# 05-SERIAL_USB.net
KiCad netlist of a schematic drawn in Altium Designer
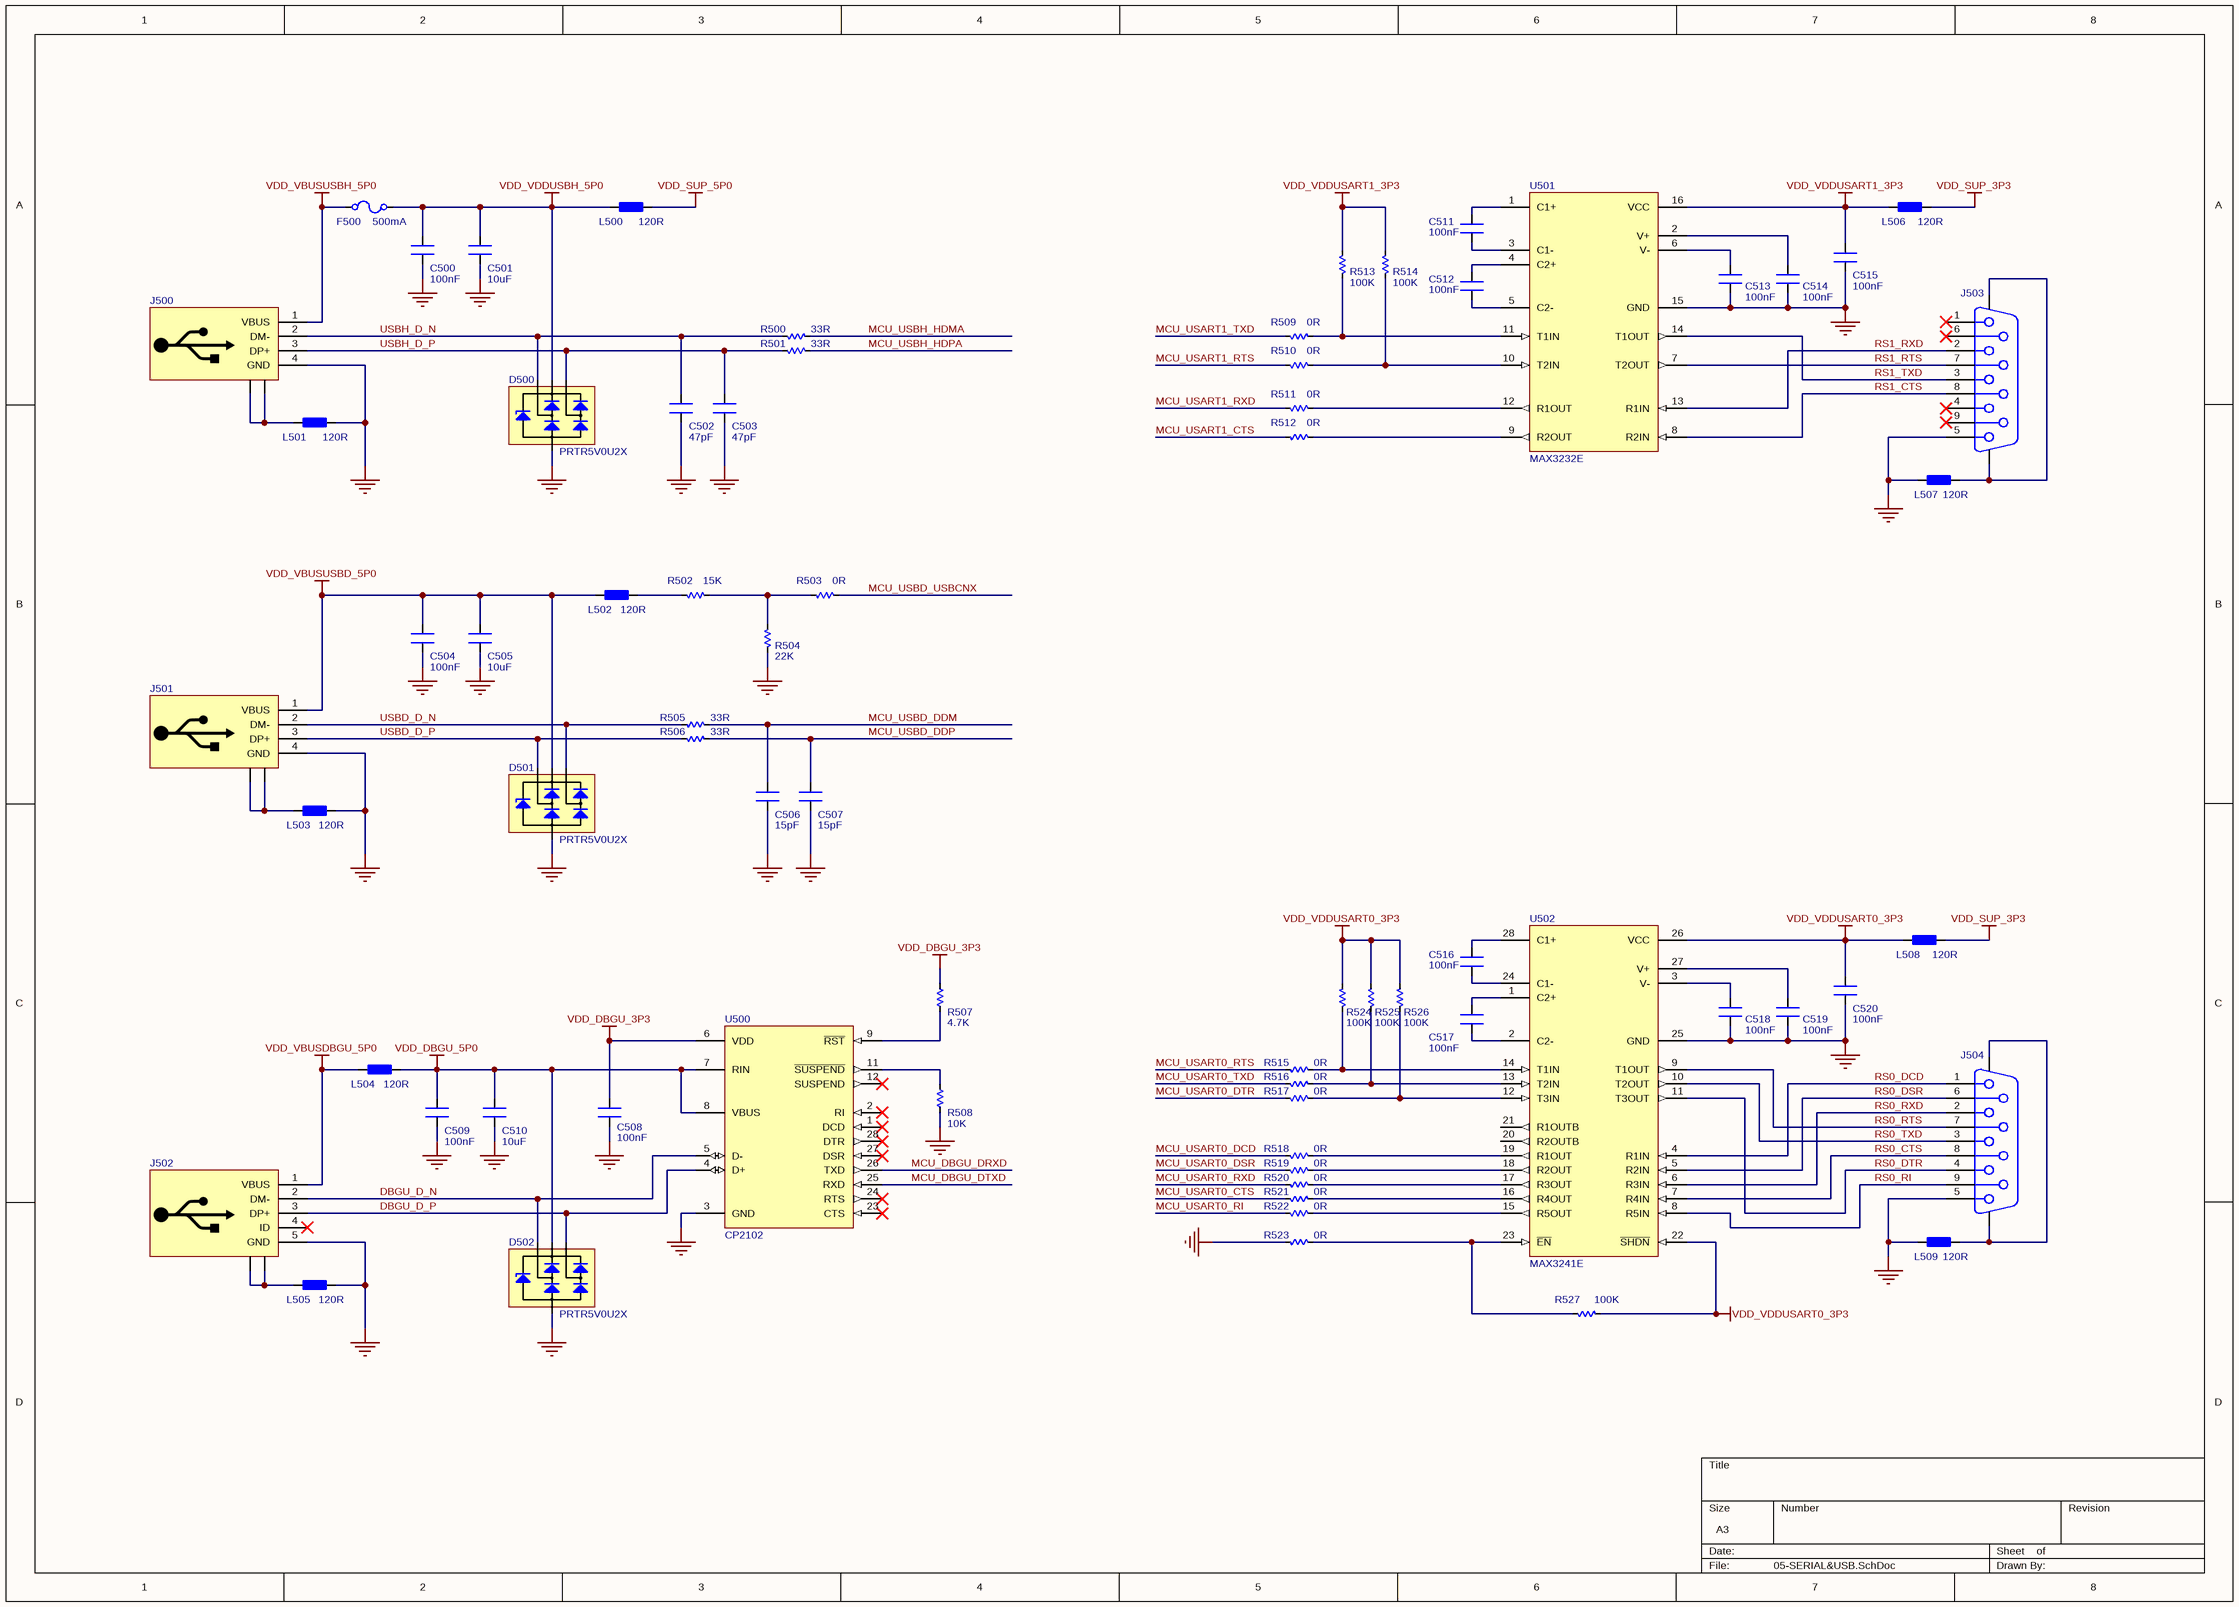
[diagram p0: 05-SERIAL&USB.SchDoc]

(export (version "E")
  (design (tool "Eeschema 10.0.6"))
  (components
    (comp (ref "C500")
      (value "100nF")
      (footprint "CN-SMD-0603")
      (description "Ceramic Capacitor SMD 0603 100nF ±20% 10V")
      (fields (field (name "Comment") "Capacitor"))
      (libsource (lib "AS50") (part "Cap"))
    )
    (comp (ref "C501")
      (value "10uF")
      (footprint "CN-SMD-0603")
      (description "Ceramic Capacitor SMD 0603 10uF ±20% 10V")
      (fields (field (name "Comment") "Capacitor"))
      (libsource (lib "AS50") (part "Cap"))
    )
    (comp (ref "C502")
      (value "47pF")
      (footprint "CN-SMD-0603")
      (description "Ceramic Capacitor SMD 0603 47pF ±20% 10V")
      (fields (field (name "Comment") "Capacitor"))
      (libsource (lib "AS50") (part "Cap"))
    )
    (comp (ref "C503")
      (value "47pF")
      (footprint "CN-SMD-0603")
      (description "Ceramic Capacitor SMD 0603 47pF ±20% 10V")
      (fields (field (name "Comment") "Capacitor"))
      (libsource (lib "AS50") (part "Cap"))
    )
    (comp (ref "C504")
      (value "100nF")
      (footprint "CN-SMD-0603")
      (description "Ceramic Capacitor SMD 0603 100nF ±20% 10V")
      (fields (field (name "Comment") "Capacitor"))
      (libsource (lib "AS50") (part "Cap"))
    )
    (comp (ref "C505")
      (value "10uF")
      (footprint "CN-SMD-0603")
      (description "Ceramic Capacitor SMD 0603 10uF ±20% 10V")
      (fields (field (name "Comment") "Capacitor"))
      (libsource (lib "AS50") (part "Cap"))
    )
    (comp (ref "C506")
      (value "15pF")
      (footprint "CN-SMD-0603")
      (description "Ceramic Capacitor SMD 0603 15pF ±20% 10V")
      (fields (field (name "Comment") "Capacitor"))
      (libsource (lib "AS50") (part "Cap"))
    )
    (comp (ref "C507")
      (value "15pF")
      (footprint "CN-SMD-0603")
      (description "Ceramic Capacitor SMD 0603 15pF ±20% 10V")
      (fields (field (name "Comment") "Capacitor"))
      (libsource (lib "AS50") (part "Cap"))
    )
    (comp (ref "C508")
      (value "100nF")
      (footprint "CN-SMD-0603")
      (description "Ceramic Capacitor SMD 0603 100nF ±20% 10V")
      (fields (field (name "Comment") "Capacitor"))
      (libsource (lib "AS50") (part "Cap"))
    )
    (comp (ref "C509")
      (value "100nF")
      (footprint "CN-SMD-0603")
      (description "Ceramic Capacitor SMD 0603 100nF ±20% 10V")
      (fields (field (name "Comment") "Capacitor"))
      (libsource (lib "AS50") (part "Cap"))
    )
    (comp (ref "C510")
      (value "10uF")
      (footprint "CN-SMD-0603")
      (description "Ceramic Capacitor SMD 0603 10uF ±20% 10V")
      (fields (field (name "Comment") "Capacitor"))
      (libsource (lib "AS50") (part "Cap"))
    )
    (comp (ref "C511")
      (value "100nF")
      (footprint "CN-SMD-0603")
      (description "Ceramic Capacitor SMD 0603 100nF ±20% 10V")
      (fields (field (name "Comment") "Capacitor"))
      (libsource (lib "AS50") (part "Cap"))
    )
    (comp (ref "C512")
      (value "100nF")
      (footprint "CN-SMD-0603")
      (description "Ceramic Capacitor SMD 0603 100nF ±20% 10V")
      (fields (field (name "Comment") "Capacitor"))
      (libsource (lib "AS50") (part "Cap"))
    )
    (comp (ref "C513")
      (value "100nF")
      (footprint "CN-SMD-0603")
      (description "Ceramic Capacitor SMD 0603 100nF ±20% 10V")
      (fields (field (name "Comment") "Capacitor"))
      (libsource (lib "AS50") (part "Cap"))
    )
    (comp (ref "C514")
      (value "100nF")
      (footprint "CN-SMD-0603")
      (description "Ceramic Capacitor SMD 0603 100nF ±20% 10V")
      (fields (field (name "Comment") "Capacitor"))
      (libsource (lib "AS50") (part "Cap"))
    )
    (comp (ref "C515")
      (value "100nF")
      (footprint "CN-SMD-0603")
      (description "Ceramic Capacitor SMD 0603 100nF ±20% 10V")
      (fields (field (name "Comment") "Capacitor"))
      (libsource (lib "AS50") (part "Cap"))
    )
    (comp (ref "C516")
      (value "100nF")
      (footprint "CN-SMD-0603")
      (description "Ceramic Capacitor SMD 0603 100nF ±20% 10V")
      (fields (field (name "Comment") "Capacitor"))
      (libsource (lib "AS50") (part "Cap"))
    )
    (comp (ref "C517")
      (value "100nF")
      (footprint "CN-SMD-0603")
      (description "Ceramic Capacitor SMD 0603 100nF ±20% 10V")
      (fields (field (name "Comment") "Capacitor"))
      (libsource (lib "AS50") (part "Cap"))
    )
    (comp (ref "C518")
      (value "100nF")
      (footprint "CN-SMD-0603")
      (description "Ceramic Capacitor SMD 0603 100nF ±20% 10V")
      (fields (field (name "Comment") "Capacitor"))
      (libsource (lib "AS50") (part "Cap"))
    )
    (comp (ref "C519")
      (value "100nF")
      (footprint "CN-SMD-0603")
      (description "Ceramic Capacitor SMD 0603 100nF ±20% 10V")
      (fields (field (name "Comment") "Capacitor"))
      (libsource (lib "AS50") (part "Cap"))
    )
    (comp (ref "C520")
      (value "100nF")
      (footprint "CN-SMD-0603")
      (description "Ceramic Capacitor SMD 0603 100nF ±20% 10V")
      (fields (field (name "Comment") "Capacitor"))
      (libsource (lib "AS50") (part "Cap"))
    )
    (comp (ref "D500")
      (value "PRTR5V0U2X")
      (footprint "SOT190P237X120-4N")
      (description "Ultra low capacitance double rail-to-rail ESD protection diode")
      (libsource (lib "AS50") (part "PRTR5V0U2X"))
    )
    (comp (ref "D501")
      (value "PRTR5V0U2X")
      (footprint "SOT190P237X120-4N")
      (description "Ultra low capacitance double rail-to-rail ESD protection diode")
      (libsource (lib "AS50") (part "PRTR5V0U2X"))
    )
    (comp (ref "D502")
      (value "PRTR5V0U2X")
      (footprint "SOT190P237X120-4N")
      (description "Ultra low capacitance double rail-to-rail ESD protection diode")
      (libsource (lib "AS50") (part "PRTR5V0U2X"))
    )
    (comp (ref "F500")
      (value "500mA")
      (footprint "FUSE-SMD-1812")
      (description "Fuse SMD1812 500mA")
      (libsource (lib "AS50") (part "FUSE"))
    )
    (comp (ref "J500")
      (value "USB-4")
      (footprint "USB_A_F_DIP_RA")
      (description "USB Male/Female type A")
      (libsource (lib "AS50") (part "USB-4"))
    )
    (comp (ref "J501")
      (value "USB-4")
      (footprint "USB_B_F_DIP")
      (description "USB Male/Female type B")
      (libsource (lib "AS50") (part "USB-4"))
    )
    (comp (ref "J502")
      (value "USB-5")
      (footprint "USB_micro-B_F_SMD-2")
      (description "USB Female type B")
      (libsource (lib "AS50") (part "USB-5"))
    )
    (comp (ref "J503")
      (value "DB9")
      (footprint "DB9_DIP_M")
      (description "DB-9 Female port")
      (libsource (lib "AS50") (part "DB9"))
    )
    (comp (ref "J504")
      (value "DB9")
      (footprint "DB9_DIP_M")
      (description "DB-9 Female port")
      (libsource (lib "AS50") (part "DB9"))
    )
    (comp (ref "L500")
      (value "120R")
      (footprint "L-SMD-0603")
      (description "Ferrite bead SMD 0603 120 Ohm @100MHz")
      (fields (field (name "Comment") "Ferrite bead"))
      (libsource (lib "AS50") (part "Ferrite bead"))
    )
    (comp (ref "L501")
      (value "120R")
      (footprint "L-SMD-0603")
      (description "Ferrite bead SMD 0603 120 Ohm @100MHz")
      (fields (field (name "Comment") "Ferrite bead"))
      (libsource (lib "AS50") (part "Ferrite bead"))
    )
    (comp (ref "L502")
      (value "120R")
      (footprint "L-SMD-0603")
      (description "Ferrite bead SMD 0603 120 Ohm @100MHz")
      (fields (field (name "Comment") "Ferrite bead"))
      (libsource (lib "AS50") (part "Ferrite bead"))
    )
    (comp (ref "L503")
      (value "120R")
      (footprint "L-SMD-0603")
      (description "Ferrite bead SMD 0603 120 Ohm @100MHz")
      (fields (field (name "Comment") "Ferrite bead"))
      (libsource (lib "AS50") (part "Ferrite bead"))
    )
    (comp (ref "L504")
      (value "120R")
      (footprint "L-SMD-0603")
      (description "Ferrite bead SMD 0603 120 Ohm @100MHz")
      (fields (field (name "Comment") "Ferrite bead"))
      (libsource (lib "AS50") (part "Ferrite bead"))
    )
    (comp (ref "L505")
      (value "120R")
      (footprint "L-SMD-0603")
      (description "Ferrite bead SMD 0603 120 Ohm @100MHz")
      (fields (field (name "Comment") "Ferrite bead"))
      (libsource (lib "AS50") (part "Ferrite bead"))
    )
    (comp (ref "L506")
      (value "120R")
      (footprint "L-SMD-0603")
      (description "Ferrite bead SMD 0603 120 Ohm @100MHz")
      (fields (field (name "Comment") "Ferrite bead"))
      (libsource (lib "AS50") (part "Ferrite bead"))
    )
    (comp (ref "L507")
      (value "120R")
      (footprint "L-SMD-0603")
      (description "Ferrite bead SMD 0603 120 Ohm @100MHz")
      (fields (field (name "Comment") "Ferrite bead"))
      (libsource (lib "AS50") (part "Ferrite bead"))
    )
    (comp (ref "L508")
      (value "120R")
      (footprint "L-SMD-0603")
      (description "Ferrite bead SMD 0603 120 Ohm @100MHz")
      (fields (field (name "Comment") "Ferrite bead"))
      (libsource (lib "AS50") (part "Ferrite bead"))
    )
    (comp (ref "L509")
      (value "120R")
      (footprint "L-SMD-0603")
      (description "Ferrite bead SMD 0603 120 Ohm @100MHz")
      (fields (field (name "Comment") "Ferrite bead"))
      (libsource (lib "AS50") (part "Ferrite bead"))
    )
    (comp (ref "R500")
      (value "33R")
      (footprint "RES-SMD-0603")
      (description "Resistor SMD 0603 33R 1% 0.1W")
      (fields (field (name "Comment") "Resistor"))
      (libsource (lib "AS50") (part "Res"))
    )
    (comp (ref "R501")
      (value "33R")
      (footprint "RES-SMD-0603")
      (description "Resistor SMD 0603 33R 1% 0.1W")
      (fields (field (name "Comment") "Resistor"))
      (libsource (lib "AS50") (part "Res"))
    )
    (comp (ref "R502")
      (value "15K")
      (footprint "RES-SMD-0603")
      (description "Resistor SMD 0603 15K 1% 0.1W")
      (fields (field (name "Comment") "Resistor"))
      (libsource (lib "AS50") (part "Res"))
    )
    (comp (ref "R503")
      (value "0R")
      (footprint "RES-SMD-0603")
      (description "Resistor SMD 0603 0R 1% 0.1W")
      (fields (field (name "Comment") "Resistor"))
      (libsource (lib "AS50") (part "Res"))
    )
    (comp (ref "R504")
      (value "22K")
      (footprint "RES-SMD-0603")
      (description "Resistor SMD 0603 22K 1% 0.1W")
      (fields (field (name "Comment") "Resistor"))
      (libsource (lib "AS50") (part "Res"))
    )
    (comp (ref "R505")
      (value "33R")
      (footprint "RES-SMD-0603")
      (description "Resistor SMD 0603 33R 1% 0.1W")
      (fields (field (name "Comment") "Resistor"))
      (libsource (lib "AS50") (part "Res"))
    )
    (comp (ref "R506")
      (value "33R")
      (footprint "RES-SMD-0603")
      (description "Resistor SMD 0603 33R 1% 0.1W")
      (fields (field (name "Comment") "Resistor"))
      (libsource (lib "AS50") (part "Res"))
    )
    (comp (ref "R507")
      (value "4.7K")
      (footprint "RES-SMD-0603")
      (description "Resistor SMD 0603 4.7K 1% 0.1W")
      (fields (field (name "Comment") "R"))
      (libsource (lib "AS50") (part "Res"))
    )
    (comp (ref "R508")
      (value "10K")
      (footprint "RES-SMD-0603")
      (description "Resistor SMD 0603 10K 1% 0.1W")
      (fields (field (name "Comment") "R"))
      (libsource (lib "AS50") (part "Res"))
    )
    (comp (ref "R509")
      (value "0R")
      (footprint "RES-SMD-0603")
      (description "Resistor SMD 0603 0R 1% 0.1W")
      (fields (field (name "Comment") "Resistor"))
      (libsource (lib "AS50") (part "Res"))
    )
    (comp (ref "R510")
      (value "0R")
      (footprint "RES-SMD-0603")
      (description "Resistor SMD 0603 0R 1% 0.1W")
      (fields (field (name "Comment") "Resistor"))
      (libsource (lib "AS50") (part "Res"))
    )
    (comp (ref "R511")
      (value "0R")
      (footprint "RES-SMD-0603")
      (description "Resistor SMD 0603 0R 1% 0.1W")
      (fields (field (name "Comment") "Resistor"))
      (libsource (lib "AS50") (part "Res"))
    )
    (comp (ref "R512")
      (value "0R")
      (footprint "RES-SMD-0603")
      (description "Resistor SMD 0603 0R 1% 0.1W")
      (fields (field (name "Comment") "Resistor"))
      (libsource (lib "AS50") (part "Res"))
    )
    (comp (ref "R513")
      (value "100K")
      (footprint "RES-SMD-0603")
      (description "Resistor SMD 0603 100K 1% 0.1W")
      (fields (field (name "Comment") "Resistor"))
      (libsource (lib "AS50") (part "Res"))
    )
    (comp (ref "R514")
      (value "100K")
      (footprint "RES-SMD-0603")
      (description "Resistor SMD 0603 100K 1% 0.1W")
      (fields (field (name "Comment") "Resistor"))
      (libsource (lib "AS50") (part "Res"))
    )
    (comp (ref "R515")
      (value "0R")
      (footprint "RES-SMD-0603")
      (description "Resistor SMD 0603 0R 1% 0.1W")
      (fields (field (name "Comment") "Resistor"))
      (libsource (lib "AS50") (part "Res"))
    )
    (comp (ref "R516")
      (value "0R")
      (footprint "RES-SMD-0603")
      (description "Resistor SMD 0603 0R 1% 0.1W")
      (fields (field (name "Comment") "Resistor"))
      (libsource (lib "AS50") (part "Res"))
    )
    (comp (ref "R517")
      (value "0R")
      (footprint "RES-SMD-0603")
      (description "Resistor SMD 0603 0R 1% 0.1W")
      (fields (field (name "Comment") "Resistor"))
      (libsource (lib "AS50") (part "Res"))
    )
    (comp (ref "R518")
      (value "0R")
      (footprint "RES-SMD-0603")
      (description "Resistor SMD 0603 0R 1% 0.1W")
      (fields (field (name "Comment") "Resistor"))
      (libsource (lib "AS50") (part "Res"))
    )
    (comp (ref "R519")
      (value "0R")
      (footprint "RES-SMD-0603")
      (description "Resistor SMD 0603 0R 1% 0.1W")
      (fields (field (name "Comment") "Resistor"))
      (libsource (lib "AS50") (part "Res"))
    )
    (comp (ref "R520")
      (value "0R")
      (footprint "RES-SMD-0603")
      (description "Resistor SMD 0603 0R 1% 0.1W")
      (fields (field (name "Comment") "Resistor"))
      (libsource (lib "AS50") (part "Res"))
    )
    (comp (ref "R521")
      (value "0R")
      (footprint "RES-SMD-0603")
      (description "Resistor SMD 0603 0R 1% 0.1W")
      (fields (field (name "Comment") "Resistor"))
      (libsource (lib "AS50") (part "Res"))
    )
    (comp (ref "R522")
      (value "0R")
      (footprint "RES-SMD-0603")
      (description "Resistor SMD 0603 0R 1% 0.1W")
      (fields (field (name "Comment") "Resistor"))
      (libsource (lib "AS50") (part "Res"))
    )
    (comp (ref "R523")
      (value "0R")
      (footprint "RES-SMD-0603")
      (description "Resistor SMD 0603 0R 1% 0.1W")
      (fields (field (name "Comment") "Resistor"))
      (libsource (lib "AS50") (part "Res"))
    )
    (comp (ref "R524")
      (value "100K")
      (footprint "RES-SMD-0603")
      (description "Resistor SMD 0603 100K 1% 0.1W")
      (fields (field (name "Comment") "Resistor"))
      (libsource (lib "AS50") (part "Res"))
    )
    (comp (ref "R525")
      (value "100K")
      (footprint "RES-SMD-0603")
      (description "Resistor SMD 0603 100K 1% 0.1W")
      (fields (field (name "Comment") "Resistor"))
      (libsource (lib "AS50") (part "Res"))
    )
    (comp (ref "R526")
      (value "100K")
      (footprint "RES-SMD-0603")
      (description "Resistor SMD 0603 100K 1% 0.1W")
      (fields (field (name "Comment") "Resistor"))
      (libsource (lib "AS50") (part "Res"))
    )
    (comp (ref "R527")
      (value "100K")
      (footprint "RES-SMD-0603")
      (description "Resistor SMD 0603 100K 1% 0.1W")
      (fields (field (name "Comment") "Resistor"))
      (libsource (lib "AS50") (part "Res"))
    )
    (comp (ref "U500")
      (value "CP2102")
      (footprint "QFN50P500X500X100_HS-29N")
      (description "Single chip USB-to-UART Bridge")
      (libsource (lib "AS50") (part "CP2102"))
    )
    (comp (ref "U501")
      (value "MAX3232E")
      (footprint "TSSOP65P640X120-16N")
      (libsource (lib "AS50") (part "MAX3232E"))
    )
    (comp (ref "U502")
      (value "MAX3241E")
      (footprint "SSOP65P780X200-28N")
      (libsource (lib "AS50") (part "MAX3241E"))
    )
  )
  (nets
    (net (code "1") (name "/DBGU_D_N") (class "Default")
      (node (ref "D502") (pin "2") (pintype "passive"))
      (node (ref "J502") (pin "2") (pinfunction "DM-_2") (pintype "passive"))
      (node (ref "U500") (pin "5") (pinfunction "D-_5") (pintype "bidirectional"))
    )
    (net (code "2") (name "/DBGU_D_P") (class "Default")
      (node (ref "D502") (pin "3") (pintype "passive"))
      (node (ref "J502") (pin "3") (pinfunction "DP+_3") (pintype "passive"))
      (node (ref "U500") (pin "4") (pinfunction "D+_4") (pintype "bidirectional"))
    )
    (net (code "3") (name "/MCU_DBGU_DRXD") (class "Default")
      (node (ref "U500") (pin "26") (pinfunction "TXD_26") (pintype "output"))
    )
    (net (code "4") (name "/MCU_DBGU_DTXD") (class "Default")
      (node (ref "U500") (pin "25") (pinfunction "RXD_25") (pintype "input"))
    )
    (net (code "5") (name "/MCU_USART0_CTS") (class "Default")
      (node (ref "R521") (pin "2") (pinfunction "2_2") (pintype "passive"))
    )
    (net (code "6") (name "/MCU_USART0_DCD") (class "Default")
      (node (ref "R518") (pin "2") (pinfunction "2_2") (pintype "passive"))
    )
    (net (code "7") (name "/MCU_USART0_DSR") (class "Default")
      (node (ref "R519") (pin "2") (pinfunction "2_2") (pintype "passive"))
    )
    (net (code "8") (name "/MCU_USART0_DTR") (class "Default")
      (node (ref "R517") (pin "2") (pinfunction "2_2") (pintype "passive"))
    )
    (net (code "9") (name "/MCU_USART0_RI") (class "Default")
      (node (ref "R522") (pin "2") (pinfunction "2_2") (pintype "passive"))
    )
    (net (code "10") (name "/MCU_USART0_RTS") (class "Default")
      (node (ref "R515") (pin "2") (pinfunction "2_2") (pintype "passive"))
    )
    (net (code "11") (name "/MCU_USART0_RXD") (class "Default")
      (node (ref "R520") (pin "2") (pinfunction "2_2") (pintype "passive"))
    )
    (net (code "12") (name "/MCU_USART0_TXD") (class "Default")
      (node (ref "R516") (pin "2") (pinfunction "2_2") (pintype "passive"))
    )
    (net (code "13") (name "/MCU_USART1_CTS") (class "Default")
      (node (ref "R512") (pin "2") (pinfunction "2_2") (pintype "passive"))
    )
    (net (code "14") (name "/MCU_USART1_RTS") (class "Default")
      (node (ref "R510") (pin "2") (pinfunction "2_2") (pintype "passive"))
    )
    (net (code "15") (name "/MCU_USART1_RXD") (class "Default")
      (node (ref "R511") (pin "2") (pinfunction "2_2") (pintype "passive"))
    )
    (net (code "16") (name "/MCU_USART1_TXD") (class "Default")
      (node (ref "R509") (pin "2") (pinfunction "2_2") (pintype "passive"))
    )
    (net (code "17") (name "/MCU_USBD_DDM") (class "Default")
      (node (ref "C506") (pin "2") (pinfunction "2_2") (pintype "passive"))
      (node (ref "R505") (pin "1") (pinfunction "1_1") (pintype "passive"))
    )
    (net (code "18") (name "/MCU_USBD_DDP") (class "Default")
      (node (ref "C507") (pin "2") (pinfunction "2_2") (pintype "passive"))
      (node (ref "R506") (pin "1") (pinfunction "1_1") (pintype "passive"))
    )
    (net (code "19") (name "/MCU_USBD_USBCNX") (class "Default")
      (node (ref "R503") (pin "1") (pinfunction "1_1") (pintype "passive"))
    )
    (net (code "20") (name "/MCU_USBH_HDMA") (class "Default")
      (node (ref "R500") (pin "1") (pinfunction "1_1") (pintype "passive"))
    )
    (net (code "21") (name "/MCU_USBH_HDPA") (class "Default")
      (node (ref "R501") (pin "1") (pinfunction "1_1") (pintype "passive"))
    )
    (net (code "22") (name "/RS0_CTS") (class "Default")
      (node (ref "J504") (pin "8") (pinfunction "CTS_8") (pintype "passive"))
      (node (ref "U502") (pin "7") (pinfunction "R4IN_7") (pintype "input"))
    )
    (net (code "23") (name "/RS0_DCD") (class "Default")
      (node (ref "J504") (pin "1") (pinfunction "DCD_1") (pintype "passive"))
      (node (ref "U502") (pin "4") (pinfunction "R1IN_4") (pintype "input"))
    )
    (net (code "24") (name "/RS0_DSR") (class "Default")
      (node (ref "J504") (pin "6") (pinfunction "DSR_6") (pintype "passive"))
      (node (ref "U502") (pin "5") (pinfunction "R2IN_5") (pintype "input"))
    )
    (net (code "25") (name "/RS0_DTR") (class "Default")
      (node (ref "J504") (pin "4") (pinfunction "DTR_4") (pintype "passive"))
      (node (ref "U502") (pin "11") (pinfunction "T3OUT_11") (pintype "output"))
    )
    (net (code "26") (name "/RS0_RI") (class "Default")
      (node (ref "J504") (pin "9") (pinfunction "RI_9") (pintype "passive"))
      (node (ref "U502") (pin "8") (pinfunction "R5IN_8") (pintype "input"))
    )
    (net (code "27") (name "/RS0_RTS") (class "Default")
      (node (ref "J504") (pin "7") (pinfunction "RTS_7") (pintype "passive"))
      (node (ref "U502") (pin "9") (pinfunction "T1OUT_9") (pintype "output"))
    )
    (net (code "28") (name "/RS0_RXD") (class "Default")
      (node (ref "J504") (pin "2") (pinfunction "RXD_2") (pintype "passive"))
      (node (ref "U502") (pin "6") (pinfunction "R3IN_6") (pintype "input"))
    )
    (net (code "29") (name "/RS0_TXD") (class "Default")
      (node (ref "J504") (pin "3") (pinfunction "TXD_3") (pintype "passive"))
      (node (ref "U502") (pin "10") (pinfunction "T2OUT_10") (pintype "output"))
    )
    (net (code "30") (name "/RS1_CTS") (class "Default")
      (node (ref "J503") (pin "8") (pinfunction "CTS_8") (pintype "passive"))
      (node (ref "U501") (pin "8") (pinfunction "R2IN_8") (pintype "input"))
    )
    (net (code "31") (name "/RS1_RTS") (class "Default")
      (node (ref "J503") (pin "7") (pinfunction "RTS_7") (pintype "passive"))
      (node (ref "U501") (pin "7") (pinfunction "T2OUT_7") (pintype "output"))
    )
    (net (code "32") (name "/RS1_RXD") (class "Default")
      (node (ref "J503") (pin "2") (pinfunction "RXD_2") (pintype "passive"))
      (node (ref "U501") (pin "13") (pinfunction "R1IN_13") (pintype "input"))
    )
    (net (code "33") (name "/RS1_TXD") (class "Default")
      (node (ref "J503") (pin "3") (pinfunction "TXD_3") (pintype "passive"))
      (node (ref "U501") (pin "14") (pinfunction "T1OUT_14") (pintype "output"))
    )
    (net (code "34") (name "/USBD_D_N") (class "Default")
      (node (ref "D501") (pin "3") (pintype "passive"))
      (node (ref "J501") (pin "2") (pinfunction "DM-_2") (pintype "passive"))
      (node (ref "R505") (pin "2") (pinfunction "2_2") (pintype "passive"))
    )
    (net (code "35") (name "/USBD_D_P") (class "Default")
      (node (ref "D501") (pin "2") (pintype "passive"))
      (node (ref "J501") (pin "3") (pinfunction "DP+_3") (pintype "passive"))
      (node (ref "R506") (pin "2") (pinfunction "2_2") (pintype "passive"))
    )
    (net (code "36") (name "/USBH_D_N") (class "Default")
      (node (ref "C502") (pin "2") (pinfunction "2_2") (pintype "passive"))
      (node (ref "D500") (pin "2") (pintype "passive"))
      (node (ref "J500") (pin "2") (pinfunction "DM-_2") (pintype "passive"))
      (node (ref "R500") (pin "2") (pinfunction "2_2") (pintype "passive"))
    )
    (net (code "37") (name "/USBH_D_P") (class "Default")
      (node (ref "C503") (pin "2") (pinfunction "2_2") (pintype "passive"))
      (node (ref "D500") (pin "3") (pintype "passive"))
      (node (ref "J500") (pin "3") (pinfunction "DP+_3") (pintype "passive"))
      (node (ref "R501") (pin "2") (pinfunction "2_2") (pintype "passive"))
    )
    (net (code "38") (name "GND") (class "Default")
      (node (ref "C500") (pin "1") (pinfunction "1_1") (pintype "passive"))
      (node (ref "C501") (pin "1") (pinfunction "1_1") (pintype "passive"))
      (node (ref "C502") (pin "1") (pinfunction "1_1") (pintype "passive"))
      (node (ref "C503") (pin "1") (pinfunction "1_1") (pintype "passive"))
      (node (ref "C504") (pin "1") (pinfunction "1_1") (pintype "passive"))
      (node (ref "C505") (pin "1") (pinfunction "1_1") (pintype "passive"))
      (node (ref "C506") (pin "1") (pinfunction "1_1") (pintype "passive"))
      (node (ref "C507") (pin "1") (pinfunction "1_1") (pintype "passive"))
      (node (ref "C508") (pin "1") (pinfunction "1_1") (pintype "passive"))
      (node (ref "C509") (pin "1") (pinfunction "1_1") (pintype "passive"))
      (node (ref "C510") (pin "1") (pinfunction "1_1") (pintype "passive"))
      (node (ref "C513") (pin "1") (pinfunction "1_1") (pintype "passive"))
      (node (ref "C514") (pin "1") (pinfunction "1_1") (pintype "passive"))
      (node (ref "C515") (pin "1") (pinfunction "1_1") (pintype "passive"))
      (node (ref "C518") (pin "1") (pinfunction "1_1") (pintype "passive"))
      (node (ref "C519") (pin "1") (pinfunction "1_1") (pintype "passive"))
      (node (ref "C520") (pin "1") (pinfunction "1_1") (pintype "passive"))
      (node (ref "D500") (pin "1") (pinfunction "GND_1") (pintype "passive"))
      (node (ref "D501") (pin "1") (pinfunction "GND_1") (pintype "passive"))
      (node (ref "D502") (pin "1") (pinfunction "GND_1") (pintype "passive"))
      (node (ref "J500") (pin "4") (pinfunction "GND_4") (pintype "passive"))
      (node (ref "J501") (pin "4") (pinfunction "GND_4") (pintype "passive"))
      (node (ref "J502") (pin "5") (pinfunction "GND_5") (pintype "passive"))
      (node (ref "J503") (pin "5") (pinfunction "GND_5") (pintype "passive"))
      (node (ref "J504") (pin "5") (pinfunction "GND_5") (pintype "passive"))
      (node (ref "L501") (pin "1") (pinfunction "1_1") (pintype "passive"))
      (node (ref "L503") (pin "2") (pinfunction "2_2") (pintype "passive"))
      (node (ref "L505") (pin "2") (pinfunction "2_2") (pintype "passive"))
      (node (ref "L507") (pin "1") (pinfunction "1_1") (pintype "passive"))
      (node (ref "L509") (pin "1") (pinfunction "1_1") (pintype "passive"))
      (node (ref "R504") (pin "2") (pinfunction "2_2") (pintype "passive"))
      (node (ref "R508") (pin "1") (pinfunction "1_1") (pintype "passive"))
      (node (ref "R523") (pin "2") (pinfunction "2_2") (pintype "passive"))
      (node (ref "U500") (pin "3") (pinfunction "GND_3") (pintype "power_in"))
      (node (ref "U501") (pin "15") (pinfunction "GND_15") (pintype "power_in"))
      (node (ref "U502") (pin "25") (pinfunction "GND_25") (pintype "power_in"))
    )
    (net (code "39") (name "Net-(J500-Pad0)") (class "Default")
      (node (ref "J500") (pin "0") (pintype "power_in"))
      (node (ref "L501") (pin "2") (pinfunction "2_2") (pintype "passive"))
    )
    (net (code "40") (name "Net-(J501-Pad0)") (class "Default")
      (node (ref "J501") (pin "0") (pintype "power_in"))
      (node (ref "L503") (pin "1") (pinfunction "1_1") (pintype "passive"))
    )
    (net (code "41") (name "Net-(J502-Pad0)") (class "Default")
      (node (ref "J502") (pin "0") (pintype "power_in"))
      (node (ref "L505") (pin "1") (pinfunction "1_1") (pintype "passive"))
    )
    (net (code "42") (name "Net-(J503-Pad10)") (class "Default")
      (node (ref "J503") (pin "10") (pintype "passive"))
      (node (ref "J503") (pin "11") (pintype "passive"))
      (node (ref "L507") (pin "2") (pinfunction "2_2") (pintype "passive"))
    )
    (net (code "43") (name "Net-(J504-Pad10)") (class "Default")
      (node (ref "J504") (pin "10") (pintype "passive"))
      (node (ref "J504") (pin "11") (pintype "passive"))
      (node (ref "L509") (pin "2") (pinfunction "2_2") (pintype "passive"))
    )
    (net (code "44") (name "Net-(L502-Pad2)") (class "Default")
      (node (ref "L502") (pin "2") (pinfunction "2_2") (pintype "passive"))
      (node (ref "R502") (pin "2") (pinfunction "2_2") (pintype "passive"))
    )
    (net (code "45") (name "Net-(R502-Pad1)") (class "Default")
      (node (ref "R502") (pin "1") (pinfunction "1_1") (pintype "passive"))
      (node (ref "R503") (pin "2") (pinfunction "2_2") (pintype "passive"))
      (node (ref "R504") (pin "1") (pinfunction "1_1") (pintype "passive"))
    )
    (net (code "46") (name "Net-(U500-~{RST})") (class "Default")
      (node (ref "R507") (pin "1") (pinfunction "1_1") (pintype "passive"))
      (node (ref "U500") (pin "9") (pinfunction "~{RST}_9") (pintype "input"))
    )
    (net (code "47") (name "Net-(U500-~{SUSPEND})") (class "Default")
      (node (ref "R508") (pin "2") (pinfunction "2_2") (pintype "passive"))
      (node (ref "U500") (pin "11") (pinfunction "~{SUSPEND}_11") (pintype "output"))
    )
    (net (code "48") (name "Net-(U501-C1+)") (class "Default")
      (node (ref "C511") (pin "2") (pinfunction "2_2") (pintype "passive"))
      (node (ref "U501") (pin "1") (pinfunction "C1+_1") (pintype "passive"))
    )
    (net (code "49") (name "Net-(U501-C1-)") (class "Default")
      (node (ref "C511") (pin "1") (pinfunction "1_1") (pintype "passive"))
      (node (ref "U501") (pin "3") (pinfunction "C1-_3") (pintype "passive"))
    )
    (net (code "50") (name "Net-(U501-C2+)") (class "Default")
      (node (ref "C512") (pin "2") (pinfunction "2_2") (pintype "passive"))
      (node (ref "U501") (pin "4") (pinfunction "C2+_4") (pintype "passive"))
    )
    (net (code "51") (name "Net-(U501-C2-)") (class "Default")
      (node (ref "C512") (pin "1") (pinfunction "1_1") (pintype "passive"))
      (node (ref "U501") (pin "5") (pinfunction "C2-_5") (pintype "passive"))
    )
    (net (code "52") (name "Net-(U501-R1OUT)") (class "Default")
      (node (ref "R511") (pin "1") (pinfunction "1_1") (pintype "passive"))
      (node (ref "U501") (pin "12") (pinfunction "R1OUT_12") (pintype "output"))
    )
    (net (code "53") (name "Net-(U501-R2OUT)") (class "Default")
      (node (ref "R512") (pin "1") (pinfunction "1_1") (pintype "passive"))
      (node (ref "U501") (pin "9") (pinfunction "R2OUT_9") (pintype "output"))
    )
    (net (code "54") (name "Net-(U501-T1IN)") (class "Default")
      (node (ref "R509") (pin "1") (pinfunction "1_1") (pintype "passive"))
      (node (ref "R513") (pin "2") (pinfunction "2_2") (pintype "passive"))
      (node (ref "U501") (pin "11") (pinfunction "T1IN_11") (pintype "input"))
    )
    (net (code "55") (name "Net-(U501-T2IN)") (class "Default")
      (node (ref "R510") (pin "1") (pinfunction "1_1") (pintype "passive"))
      (node (ref "R514") (pin "2") (pinfunction "2_2") (pintype "passive"))
      (node (ref "U501") (pin "10") (pinfunction "T2IN_10") (pintype "input"))
    )
    (net (code "56") (name "Net-(U501-V+)") (class "Default")
      (node (ref "C514") (pin "2") (pinfunction "2_2") (pintype "passive"))
      (node (ref "U501") (pin "2") (pinfunction "V+_2") (pintype "power_in"))
    )
    (net (code "57") (name "Net-(U501-V-)") (class "Default")
      (node (ref "C513") (pin "2") (pinfunction "2_2") (pintype "passive"))
      (node (ref "U501") (pin "6") (pinfunction "V-_6") (pintype "power_in"))
    )
    (net (code "58") (name "Net-(U502-C1+)") (class "Default")
      (node (ref "C516") (pin "2") (pinfunction "2_2") (pintype "passive"))
      (node (ref "U502") (pin "28") (pinfunction "C1+_28") (pintype "passive"))
    )
    (net (code "59") (name "Net-(U502-C1-)") (class "Default")
      (node (ref "C516") (pin "1") (pinfunction "1_1") (pintype "passive"))
      (node (ref "U502") (pin "24") (pinfunction "C1-_24") (pintype "passive"))
    )
    (net (code "60") (name "Net-(U502-C2+)") (class "Default")
      (node (ref "C517") (pin "2") (pinfunction "2_2") (pintype "passive"))
      (node (ref "U502") (pin "1") (pinfunction "C2+_1") (pintype "passive"))
    )
    (net (code "61") (name "Net-(U502-C2-)") (class "Default")
      (node (ref "C517") (pin "1") (pinfunction "1_1") (pintype "passive"))
      (node (ref "U502") (pin "2") (pinfunction "C2-_2") (pintype "passive"))
    )
    (net (code "62") (name "Net-(U502-R1OUT)") (class "Default")
      (node (ref "R518") (pin "1") (pinfunction "1_1") (pintype "passive"))
      (node (ref "U502") (pin "19") (pinfunction "R1OUT_19") (pintype "output"))
    )
    (net (code "63") (name "Net-(U502-R2OUT)") (class "Default")
      (node (ref "R519") (pin "1") (pinfunction "1_1") (pintype "passive"))
      (node (ref "U502") (pin "18") (pinfunction "R2OUT_18") (pintype "output"))
    )
    (net (code "64") (name "Net-(U502-R3OUT)") (class "Default")
      (node (ref "R520") (pin "1") (pinfunction "1_1") (pintype "passive"))
      (node (ref "U502") (pin "17") (pinfunction "R3OUT_17") (pintype "output"))
    )
    (net (code "65") (name "Net-(U502-R4OUT)") (class "Default")
      (node (ref "R521") (pin "1") (pinfunction "1_1") (pintype "passive"))
      (node (ref "U502") (pin "16") (pinfunction "R4OUT_16") (pintype "output"))
    )
    (net (code "66") (name "Net-(U502-R5OUT)") (class "Default")
      (node (ref "R522") (pin "1") (pinfunction "1_1") (pintype "passive"))
      (node (ref "U502") (pin "15") (pinfunction "R5OUT_15") (pintype "output"))
    )
    (net (code "67") (name "Net-(U502-T1IN)") (class "Default")
      (node (ref "R515") (pin "1") (pinfunction "1_1") (pintype "passive"))
      (node (ref "R524") (pin "2") (pinfunction "2_2") (pintype "passive"))
      (node (ref "U502") (pin "14") (pinfunction "T1IN_14") (pintype "input"))
    )
    (net (code "68") (name "Net-(U502-T2IN)") (class "Default")
      (node (ref "R516") (pin "1") (pinfunction "1_1") (pintype "passive"))
      (node (ref "R525") (pin "2") (pinfunction "2_2") (pintype "passive"))
      (node (ref "U502") (pin "13") (pinfunction "T2IN_13") (pintype "input"))
    )
    (net (code "69") (name "Net-(U502-T3IN)") (class "Default")
      (node (ref "R517") (pin "1") (pinfunction "1_1") (pintype "passive"))
      (node (ref "R526") (pin "2") (pinfunction "2_2") (pintype "passive"))
      (node (ref "U502") (pin "12") (pinfunction "T3IN_12") (pintype "input"))
    )
    (net (code "70") (name "Net-(U502-V+)") (class "Default")
      (node (ref "C519") (pin "2") (pinfunction "2_2") (pintype "passive"))
      (node (ref "U502") (pin "27") (pinfunction "V+_27") (pintype "power_in"))
    )
    (net (code "71") (name "Net-(U502-V-)") (class "Default")
      (node (ref "C518") (pin "2") (pinfunction "2_2") (pintype "passive"))
      (node (ref "U502") (pin "3") (pinfunction "V-_3") (pintype "power_in"))
    )
    (net (code "72") (name "Net-(U502-~{EN})") (class "Default")
      (node (ref "R523") (pin "1") (pinfunction "1_1") (pintype "passive"))
      (node (ref "R527") (pin "2") (pinfunction "2_2") (pintype "passive"))
      (node (ref "U502") (pin "23") (pinfunction "~{EN}_23") (pintype "input"))
    )
    (net (code "73") (name "VDD_DBGU_3P3") (class "Default")
      (node (ref "C508") (pin "2") (pinfunction "2_2") (pintype "passive"))
      (node (ref "R507") (pin "2") (pinfunction "2_2") (pintype "passive"))
      (node (ref "U500") (pin "6") (pinfunction "VDD_6") (pintype "power_in"))
    )
    (net (code "74") (name "VDD_DBGU_5P0") (class "Default")
      (node (ref "C509") (pin "2") (pinfunction "2_2") (pintype "passive"))
      (node (ref "C510") (pin "2") (pinfunction "2_2") (pintype "passive"))
      (node (ref "D502") (pin "4") (pinfunction "VDD_4") (pintype "passive"))
      (node (ref "L504") (pin "2") (pinfunction "2_2") (pintype "passive"))
      (node (ref "U500") (pin "7") (pinfunction "RIN_7") (pintype "power_in"))
      (node (ref "U500") (pin "8") (pinfunction "VBUS_8") (pintype "power_in"))
    )
    (net (code "75") (name "VDD_SUP_3P3") (class "Default")
      (node (ref "L506") (pin "2") (pinfunction "2_2") (pintype "passive"))
      (node (ref "L508") (pin "2") (pinfunction "2_2") (pintype "passive"))
    )
    (net (code "76") (name "VDD_SUP_5P0") (class "Default")
      (node (ref "L500") (pin "2") (pinfunction "2_2") (pintype "passive"))
    )
    (net (code "77") (name "VDD_VBUSDBGU_5P0") (class "Default")
      (node (ref "J502") (pin "1") (pinfunction "VBUS_1") (pintype "passive"))
      (node (ref "L504") (pin "1") (pinfunction "1_1") (pintype "passive"))
    )
    (net (code "78") (name "VDD_VBUSUSBD_5P0") (class "Default")
      (node (ref "C504") (pin "2") (pinfunction "2_2") (pintype "passive"))
      (node (ref "C505") (pin "2") (pinfunction "2_2") (pintype "passive"))
      (node (ref "D501") (pin "4") (pinfunction "VDD_4") (pintype "passive"))
      (node (ref "J501") (pin "1") (pinfunction "VBUS_1") (pintype "passive"))
      (node (ref "L502") (pin "1") (pinfunction "1_1") (pintype "passive"))
    )
    (net (code "79") (name "VDD_VBUSUSBH_5P0") (class "Default")
      (node (ref "F500") (pin "1") (pintype "passive"))
      (node (ref "J500") (pin "1") (pinfunction "VBUS_1") (pintype "passive"))
    )
    (net (code "80") (name "VDD_VDDUSART0_3P3") (class "Default")
      (node (ref "C520") (pin "2") (pinfunction "2_2") (pintype "passive"))
      (node (ref "L508") (pin "1") (pinfunction "1_1") (pintype "passive"))
      (node (ref "R524") (pin "1") (pinfunction "1_1") (pintype "passive"))
      (node (ref "R525") (pin "1") (pinfunction "1_1") (pintype "passive"))
      (node (ref "R526") (pin "1") (pinfunction "1_1") (pintype "passive"))
      (node (ref "R527") (pin "1") (pinfunction "1_1") (pintype "passive"))
      (node (ref "U502") (pin "22") (pinfunction "~{SHDN}_22") (pintype "input"))
      (node (ref "U502") (pin "26") (pinfunction "VCC_26") (pintype "power_in"))
    )
    (net (code "81") (name "VDD_VDDUSART1_3P3") (class "Default")
      (node (ref "C515") (pin "2") (pinfunction "2_2") (pintype "passive"))
      (node (ref "L506") (pin "1") (pinfunction "1_1") (pintype "passive"))
      (node (ref "R513") (pin "1") (pinfunction "1_1") (pintype "passive"))
      (node (ref "R514") (pin "1") (pinfunction "1_1") (pintype "passive"))
      (node (ref "U501") (pin "16") (pinfunction "VCC_16") (pintype "power_in"))
    )
    (net (code "82") (name "VDD_VDDUSBH_5P0") (class "Default")
      (node (ref "C500") (pin "2") (pinfunction "2_2") (pintype "passive"))
      (node (ref "C501") (pin "2") (pinfunction "2_2") (pintype "passive"))
      (node (ref "D500") (pin "4") (pinfunction "VDD_4") (pintype "passive"))
      (node (ref "F500") (pin "2") (pintype "passive"))
      (node (ref "L500") (pin "1") (pinfunction "1_1") (pintype "passive"))
    )
    (net (code "83") (name "unconnected-(J502-ID-Pad4)") (class "Default")
      (node (ref "J502") (pin "4") (pinfunction "ID_4") (pintype "passive+no_connect"))
    )
    (net (code "84") (name "unconnected-(J503-DCD-Pad1)") (class "Default")
      (node (ref "J503") (pin "1") (pinfunction "DCD_1") (pintype "passive+no_connect"))
    )
    (net (code "85") (name "unconnected-(J503-DSR-Pad6)") (class "Default")
      (node (ref "J503") (pin "6") (pinfunction "DSR_6") (pintype "passive+no_connect"))
    )
    (net (code "86") (name "unconnected-(J503-DTR-Pad4)") (class "Default")
      (node (ref "J503") (pin "4") (pinfunction "DTR_4") (pintype "passive+no_connect"))
    )
    (net (code "87") (name "unconnected-(J503-RI-Pad9)") (class "Default")
      (node (ref "J503") (pin "9") (pinfunction "RI_9") (pintype "passive+no_connect"))
    )
    (net (code "88") (name "unconnected-(U500-CTS-Pad23)") (class "Default")
      (node (ref "U500") (pin "23") (pinfunction "CTS_23") (pintype "input+no_connect"))
    )
    (net (code "89") (name "unconnected-(U500-DCD-Pad1)") (class "Default")
      (node (ref "U500") (pin "1") (pinfunction "DCD_1") (pintype "input+no_connect"))
    )
    (net (code "90") (name "unconnected-(U500-DSR-Pad27)") (class "Default")
      (node (ref "U500") (pin "27") (pinfunction "DSR_27") (pintype "input+no_connect"))
    )
    (net (code "91") (name "unconnected-(U500-DTR-Pad28)") (class "Default")
      (node (ref "U500") (pin "28") (pinfunction "DTR_28") (pintype "output+no_connect"))
    )
    (net (code "92") (name "unconnected-(U500-RI-Pad2)") (class "Default")
      (node (ref "U500") (pin "2") (pinfunction "RI_2") (pintype "input+no_connect"))
    )
    (net (code "93") (name "unconnected-(U500-RTS-Pad24)") (class "Default")
      (node (ref "U500") (pin "24") (pinfunction "RTS_24") (pintype "output+no_connect"))
    )
    (net (code "94") (name "unconnected-(U500-SUSPEND-Pad12)") (class "Default")
      (node (ref "U500") (pin "12") (pinfunction "SUSPEND_12") (pintype "output+no_connect"))
    )
    (net (code "95") (name "unconnected-(U502-R1OUTB-Pad21)") (class "Default")
      (node (ref "U502") (pin "21") (pinfunction "R1OUTB_21") (pintype "output"))
    )
    (net (code "96") (name "unconnected-(U502-R2OUTB-Pad20)") (class "Default")
      (node (ref "U502") (pin "20") (pinfunction "R2OUTB_20") (pintype "output"))
    )
  )
)
